# 220VAC_to_48V.net
KiCad netlist of a schematic drawn in Altium Designer
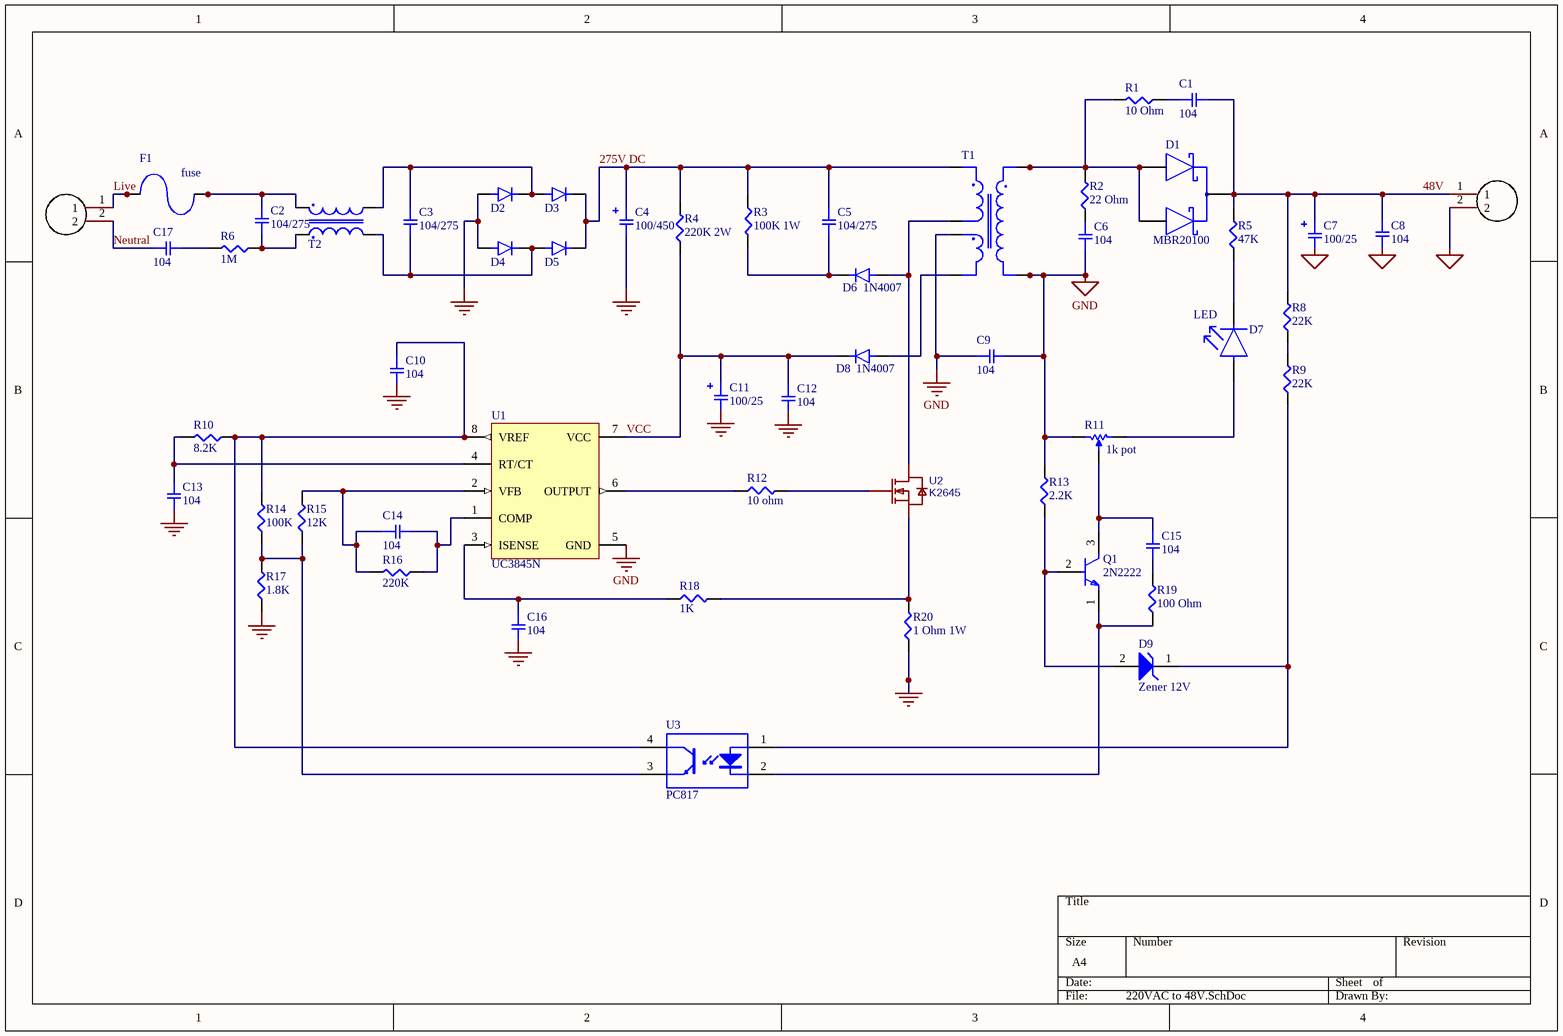
[diagram p0: 220VAC to 48V.SchDoc]

(export (version "E")
  (design (tool "Eeschema 10.0.6"))
  (components
    (comp (ref "C1") (value "104") (footprint "C-1") (libsource (lib "AC220_to_48V") (part "CAPACITOR 104")))
    (comp (ref "C2")
      (value "104/275")
      (footprint "C-15")
      (libsource (lib "AC220_to_48V") (part "CAPACITOR 104/275"))
    )
    (comp (ref "C3")
      (value "104/275")
      (footprint "C-15")
      (libsource (lib "AC220_to_48V") (part "CAPACITOR 104/275"))
    )
    (comp (ref "C4")
      (value "100/450")
      (footprint "C5B2.5")
      (libsource (lib "AC220_to_48V") (part "CAPACITOR 100/450"))
    )
    (comp (ref "C5")
      (value "104/275")
      (footprint "C-15")
      (libsource (lib "AC220_to_48V") (part "CAPACITOR 104/275"))
    )
    (comp (ref "C6") (value "104") (footprint "C-1") (libsource (lib "AC220_to_48V") (part "CAPACITOR 104")))
    (comp (ref "C7")
      (value "100/25")
      (footprint "C2.5-2")
      (libsource (lib "AC220_to_48V") (part "CAPACITOR 100/25"))
    )
    (comp (ref "C8") (value "104") (footprint "C-1") (libsource (lib "AC220_to_48V") (part "CAPACITOR 104")))
    (comp (ref "C9") (value "104") (footprint "C-1") (libsource (lib "AC220_to_48V") (part "CAPACITOR 104")))
    (comp (ref "C10") (value "104") (footprint "C-1") (libsource (lib "AC220_to_48V") (part "CAPACITOR 104")))
    (comp (ref "C11")
      (value "100/25")
      (footprint "C2.5-2")
      (libsource (lib "AC220_to_48V") (part "CAPACITOR 100/25"))
    )
    (comp (ref "C12") (value "104") (footprint "C-1") (libsource (lib "AC220_to_48V") (part "CAPACITOR 104")))
    (comp (ref "C13") (value "104") (footprint "C-1") (libsource (lib "AC220_to_48V") (part "CAPACITOR 104")))
    (comp (ref "C14") (value "104") (footprint "C-1") (libsource (lib "AC220_to_48V") (part "CAPACITOR 104")))
    (comp (ref "C15") (value "104") (footprint "C-1") (libsource (lib "AC220_to_48V") (part "CAPACITOR 104")))
    (comp (ref "C16") (value "104") (footprint "C-1") (libsource (lib "AC220_to_48V") (part "CAPACITOR 104")))
    (comp (ref "C17") (value "104") (footprint "C-1") (libsource (lib "AC220_to_48V") (part "CAPACITOR 104")))
    (comp (ref "CN1")
      (value "WJ2EDGRC-5.08-2P")
      (footprint "Terminal Block P5.08-2P")
      (fields (field (name "MANUFACTURER") "KANGNEX(康奈克斯电气)"))
      (libsource (lib "Terminal Block P5.08-2P") (part "WJ2EDGRC-5.08-2P"))
    )
    (comp (ref "CN2")
      (value "WJ2EDGRC-5.08-2P")
      (footprint "Terminal Block P5.08-2P")
      (fields (field (name "MANUFACTURER") "KANGNEX(康奈克斯电气)"))
      (libsource (lib "Terminal Block P5.08-2P") (part "WJ2EDGRC-5.08-2P"))
    )
    (comp (ref "D1")
      (value "MBR20100")
      (footprint "FP-MBR20100CT-E3-4W-MFG")
      (libsource (lib "MBR20100 schottky diode TH") (part "CMP-00030-42878425-1"))
    )
    (comp (ref "D2")
      (value "1N4007")
      (footprint "FP-1N4007-MFG")
      (description "DIODE GEN PURP 1KV 1A DO204AL")
      (fields
        (field (name "OCTOPART") "https://octopart.com/1n4007-e3%2F54-vishay-39548207")
        (field (name "MANUFACTURER") "Vishay")
      )
      (libsource (lib "1N4007") (part "CMP-02540-000046-1"))
    )
    (comp (ref "D3")
      (value "1N4007")
      (footprint "FP-1N4007-MFG")
      (description "DIODE GEN PURP 1KV 1A DO204AL")
      (fields
        (field (name "OCTOPART") "https://octopart.com/1n4007-e3%2F54-vishay-39548207")
        (field (name "MANUFACTURER") "Vishay")
      )
      (libsource (lib "1N4007") (part "CMP-02540-000046-1"))
    )
    (comp (ref "D4")
      (value "1N4007")
      (footprint "FP-1N4007-MFG")
      (description "DIODE GEN PURP 1KV 1A DO204AL")
      (fields
        (field (name "OCTOPART") "https://octopart.com/1n4007-e3%2F54-vishay-39548207")
        (field (name "MANUFACTURER") "Vishay")
      )
      (libsource (lib "1N4007") (part "CMP-02540-000046-1"))
    )
    (comp (ref "D5")
      (value "1N4007")
      (footprint "FP-1N4007-MFG")
      (description "DIODE GEN PURP 1KV 1A DO204AL")
      (fields
        (field (name "OCTOPART") "https://octopart.com/1n4007-e3%2F54-vishay-39548207")
        (field (name "MANUFACTURER") "Vishay")
      )
      (libsource (lib "1N4007") (part "CMP-02540-000046-1"))
    )
    (comp (ref "D6")
      (value "1N4007")
      (footprint "FP-1N4007-MFG")
      (description "DIODE GEN PURP 1KV 1A DO204AL")
      (fields
        (field (name "OCTOPART") "https://octopart.com/1n4007-e3%2F54-vishay-39548207")
        (field (name "MANUFACTURER") "Vishay")
      )
      (libsource (lib "1N4007") (part "CMP-02540-000046-1"))
    )
    (comp (ref "D7")
      (value "LED")
      (footprint "FP-HLMP-1719-MFG")
      (description "IR LED SFH480")
      (fields
        (field (name "MANUFACTURER") "Broadcom")
        (field (name "OCTOPART") "https://octopart.com/hlmp-1719-broadcom-71130405")
      )
      (libsource (lib "IR LED SFH480") (part "CMP-2000-06410-2"))
    )
    (comp (ref "D8")
      (value "1N4007")
      (footprint "FP-1N4007-MFG")
      (description "DIODE GEN PURP 1KV 1A DO204AL")
      (fields
        (field (name "OCTOPART") "https://octopart.com/1n4007-e3%2F54-vishay-39548207")
        (field (name "MANUFACTURER") "Vishay")
      )
      (libsource (lib "1N4007") (part "CMP-02540-000046-1"))
    )
    (comp (ref "D9")
      (value "Zener 12V")
      (footprint "ONSC-SURMETIC40-2-017AA-01")
      (description "Diode, Zener, Vr 12V, If 200mA, Pkg DO-41, Vf 1.2V, Tj +175C, Cs 380mA, Pd 1.3W, Ir 21mA")
      (fields (field (name "MANUFACTURER") "Vishay") (field (name "MANUFACTURER PART NUMBER") "1N4742A-TR"))
      (libsource (lib "1N4742 Zener 12V TH") (part "1N4742A-TR"))
    )
    (comp (ref "F1") (value "fuse") (footprint "SHK20L") (libsource (lib "AC220_to_48V") (part "fuse")))
    (comp (ref "Q1")
      (value "2N2222")
      (footprint "FP-JAN2N2222A-MFG")
      (description "TRANS NPN 50V 0.8A TO218")
      (libsource (lib "2N2222") (part "CMP-06366-000013-1"))
    )
    (comp (ref "R1")
      (value "10 Ohm")
      (footprint "R7-5")
      (libsource (lib "AC220_to_48V") (part "RESISTOR 1/4W"))
    )
    (comp (ref "R2")
      (value "22 Ohm")
      (footprint "R7-5")
      (libsource (lib "AC220_to_48V") (part "RESISTOR 1/4W"))
    )
    (comp (ref "R3")
      (value "100K 1W")
      (footprint "R-12,5")
      (libsource (lib "AC220_to_48V") (part "RESISTOR 2W"))
    )
    (comp (ref "R4")
      (value "220K 2W")
      (footprint "R-12,5")
      (libsource (lib "AC220_to_48V") (part "RESISTOR 2W"))
    )
    (comp (ref "R5") (value "47K") (footprint "R7-5") (libsource (lib "AC220_to_48V") (part "RESISTOR 1/4W")))
    (comp (ref "R6") (value "1M") (footprint "R7-5") (libsource (lib "AC220_to_48V") (part "RESISTOR 1/4W")))
    (comp (ref "R8") (value "22K") (footprint "R7-5") (libsource (lib "AC220_to_48V") (part "RESISTOR 1/4W")))
    (comp (ref "R9") (value "22K") (footprint "R7-5") (libsource (lib "AC220_to_48V") (part "RESISTOR 1/4W")))
    (comp (ref "R10")
      (value "8.2K")
      (footprint "R7-5")
      (libsource (lib "AC220_to_48V") (part "RESISTOR 1/4W"))
    )
    (comp (ref "R11")
      (value "1k pot")
      (footprint "BOUR-3296W-1-3")
      (description "Square Trimpot(R) Trimming Potentiometer, 1000 Ohm, -55 to 125 degC, 3-Pin THD, RoHS, Tube")
      (fields (field (name "TOLERANCE") "1%"))
      (libsource (lib "1k pot TH") (part "CMP-1747-00002-1"))
    )
    (comp (ref "R12")
      (value "10 ohm")
      (footprint "R7-5")
      (libsource (lib "AC220_to_48V") (part "RESISTOR 1/4W"))
    )
    (comp (ref "R13")
      (value "2.2K")
      (footprint "R7-5")
      (libsource (lib "AC220_to_48V") (part "RESISTOR 1/4W"))
    )
    (comp (ref "R14")
      (value "100K")
      (footprint "R7-5")
      (libsource (lib "AC220_to_48V") (part "RESISTOR 1/4W"))
    )
    (comp (ref "R15")
      (value "12K")
      (footprint "R7-5")
      (libsource (lib "AC220_to_48V") (part "RESISTOR 1/4W"))
    )
    (comp (ref "R16")
      (value "220K")
      (footprint "R7-5")
      (libsource (lib "AC220_to_48V") (part "RESISTOR 1/4W"))
    )
    (comp (ref "R17")
      (value "1.8K")
      (footprint "R7-5")
      (libsource (lib "AC220_to_48V") (part "RESISTOR 1/4W"))
    )
    (comp (ref "R18") (value "1K") (footprint "R7-5") (libsource (lib "AC220_to_48V") (part "RESISTOR 1/4W")))
    (comp (ref "R19")
      (value "100 Ohm")
      (footprint "R7-5")
      (libsource (lib "AC220_to_48V") (part "RESISTOR 1/4W"))
    )
    (comp (ref "R20")
      (value "1 Ohm 1W")
      (footprint "R-12,5")
      (libsource (lib "AC220_to_48V") (part "RESISTOR 2W"))
    )
    (comp (ref "T1")
      (value "Ideal Transformer With Central Tap")
      (footprint "ST-D1")
      (libsource (lib "AC220_to_48V") (part "Transformer With Central Tap Ideal_1"))
    )
    (comp (ref "T2")
      (value "common mode choke")
      (footprint "DFKH14")
      (libsource (lib "AC220_to_48V") (part "Transformer With Central Tap Ideal"))
    )
    (comp (ref "U1")
      (value "UC3845N")
      (footprint "P0008A")
      (fields (field (name "MANUFACTURER") "Texas Instruments"))
      (libsource (lib "UC3845AN") (part "CMP-0319-00305-2"))
    )
    (comp (ref "U2")
      (value "K2645")
      (footprint "TO-220-3_L10.5-W4.8-P2.54-L")
      (fields
        (field (name "MANUFACTURER") "VBsemi(微碧半导体)")
        (field (name "MANUFACTURER PART") "2SK2645-01MR-VB")
        (field (name "CONTRIBUTOR") "lcsc")
      )
      (libsource (lib "2SK2645") (part "2SK2645-01MR-VB"))
    )
    (comp (ref "U3")
      (value "PC817")
      (footprint "LTST-LTV-817-4")
      (fields (field (name "MANUFACTURER") "Lite-On"))
      (libsource (lib "PC817") (part "CMP-2000-06632-1"))
    )
  )
  (nets
    (net (code "1") (name "/48V") (class "Default")
      (node (ref "C1") (pin "2") (pinfunction "2_2") (pintype "passive"))
      (node (ref "C7") (pin "1") (pinfunction "1_1") (pintype "passive"))
      (node (ref "C8") (pin "2") (pinfunction "2_2") (pintype "passive"))
      (node (ref "CN1") (pin "1") (pinfunction "1_1") (pintype "passive"))
      (node (ref "D1") (pin "2") (pinfunction "COMMON_CATHODE_2") (pintype "passive"))
      (node (ref "R5") (pin "2") (pinfunction "2_2") (pintype "passive"))
      (node (ref "R8") (pin "2") (pinfunction "2_2") (pintype "passive"))
    )
    (net (code "2") (name "/275V DC") (class "Default")
      (node (ref "C4") (pin "1") (pinfunction "1_1") (pintype "passive"))
      (node (ref "C5") (pin "1") (pinfunction "1_1") (pintype "passive"))
      (node (ref "D3") (pin "1") (pinfunction "C_1") (pintype "passive"))
      (node (ref "D5") (pin "1") (pinfunction "C_1") (pintype "passive"))
      (node (ref "R3") (pin "1") (pinfunction "1_1") (pintype "passive"))
      (node (ref "R4") (pin "2") (pinfunction "2_2") (pintype "passive"))
      (node (ref "T1") (pin "7") (pinfunction "7_7") (pintype "passive"))
    )
    (net (code "3") (name "/Live") (class "Default")
      (node (ref "CN2") (pin "1") (pinfunction "1_1") (pintype "passive"))
      (node (ref "F1") (pin "1A") (pinfunction "1A_1A") (pintype "passive"))
      (node (ref "F1") (pin "1B") (pinfunction "1B_1B") (pintype "passive"))
    )
    (net (code "4") (name "/Neutral") (class "Default")
      (node (ref "C17") (pin "1") (pinfunction "1_1") (pintype "passive"))
      (node (ref "CN2") (pin "2") (pinfunction "2_2") (pintype "passive"))
    )
    (net (code "5") (name "/VCC") (class "Default")
      (node (ref "C11") (pin "1") (pinfunction "1_1") (pintype "passive"))
      (node (ref "C12") (pin "1") (pinfunction "1_1") (pintype "passive"))
      (node (ref "D8") (pin "1") (pinfunction "C_1") (pintype "passive"))
      (node (ref "R4") (pin "1") (pinfunction "1_1") (pintype "passive"))
      (node (ref "U1") (pin "7") (pinfunction "VCC_7") (pintype "power_in"))
    )
    (net (code "6") (name "GND") (class "Default")
      (node (ref "C10") (pin "2") (pinfunction "2_2") (pintype "passive"))
      (node (ref "C11") (pin "2") (pinfunction "2_2") (pintype "passive"))
      (node (ref "C12") (pin "2") (pinfunction "2_2") (pintype "passive"))
      (node (ref "C13") (pin "1") (pinfunction "1_1") (pintype "passive"))
      (node (ref "C16") (pin "2") (pinfunction "2_2") (pintype "passive"))
      (node (ref "C4") (pin "2") (pinfunction "2_2") (pintype "passive"))
      (node (ref "C6") (pin "2") (pinfunction "2_2") (pintype "passive"))
      (node (ref "C7") (pin "2") (pinfunction "2_2") (pintype "passive"))
      (node (ref "C8") (pin "1") (pinfunction "1_1") (pintype "passive"))
      (node (ref "C9") (pin "1") (pinfunction "1_1") (pintype "passive"))
      (node (ref "C9") (pin "2") (pinfunction "2_2") (pintype "passive"))
      (node (ref "CN1") (pin "2") (pinfunction "2_2") (pintype "passive"))
      (node (ref "D2") (pin "2") (pinfunction "A_2") (pintype "passive"))
      (node (ref "D4") (pin "2") (pinfunction "A_2") (pintype "passive"))
      (node (ref "R11") (pin "3") (pinfunction "B_3") (pintype "passive"))
      (node (ref "R13") (pin "2") (pinfunction "2_2") (pintype "passive"))
      (node (ref "R17") (pin "1") (pinfunction "1_1") (pintype "passive"))
      (node (ref "R20") (pin "1") (pinfunction "1_1") (pintype "passive"))
      (node (ref "T1") (pin "1") (pinfunction "1_1") (pintype "passive"))
      (node (ref "T1") (pin "2") (pinfunction "2_2") (pintype "passive"))
      (node (ref "T1") (pin "8") (pinfunction "8_8") (pintype "passive"))
      (node (ref "U1") (pin "5") (pinfunction "GND_5") (pintype "power_in"))
    )
    (net (code "7") (name "Net-(C1-Pad1)") (class "Default")
      (node (ref "C1") (pin "1") (pinfunction "1_1") (pintype "passive"))
      (node (ref "R1") (pin "1") (pinfunction "1_1") (pintype "passive"))
    )
    (net (code "8") (name "Net-(C2-Pad1)") (class "Default")
      (node (ref "C2") (pin "1") (pinfunction "1_1") (pintype "passive"))
      (node (ref "F1") (pin "2A") (pinfunction "2A_2A") (pintype "passive"))
      (node (ref "F1") (pin "2B") (pinfunction "2B_2B") (pintype "passive"))
      (node (ref "T2") (pin "4") (pinfunction "4_4") (pintype "passive"))
    )
    (net (code "9") (name "Net-(C2-Pad2)") (class "Default")
      (node (ref "C2") (pin "2") (pinfunction "2_2") (pintype "passive"))
      (node (ref "R6") (pin "1") (pinfunction "1_1") (pintype "passive"))
      (node (ref "T2") (pin "1") (pinfunction "1_1") (pintype "passive"))
    )
    (net (code "10") (name "Net-(C6-Pad1)") (class "Default")
      (node (ref "C6") (pin "1") (pinfunction "1_1") (pintype "passive"))
      (node (ref "R2") (pin "1") (pinfunction "1_1") (pintype "passive"))
    )
    (net (code "11") (name "Net-(C15-Pad2)") (class "Default")
      (node (ref "C15") (pin "2") (pinfunction "2_2") (pintype "passive"))
      (node (ref "R19") (pin "2") (pinfunction "2_2") (pintype "passive"))
    )
    (net (code "12") (name "Net-(C17-Pad2)") (class "Default")
      (node (ref "C17") (pin "2") (pinfunction "2_2") (pintype "passive"))
      (node (ref "R6") (pin "2") (pinfunction "2_2") (pintype "passive"))
    )
    (net (code "13") (name "Net-(D1-1_ANODE)") (class "Default")
      (node (ref "D1") (pin "1") (pinfunction "1_ANODE_1") (pintype "passive"))
      (node (ref "D1") (pin "3") (pinfunction "2_ANODE_3") (pintype "passive"))
      (node (ref "R1") (pin "2") (pinfunction "2_2") (pintype "passive"))
      (node (ref "T1") (pin "5") (pinfunction "5_5") (pintype "passive"))
      (node (ref "T1") (pin "6") (pinfunction "6_6") (pintype "passive"))
    )
    (net (code "14") (name "Net-(D2-C)") (class "Default")
      (node (ref "C3") (pin "1") (pinfunction "1_1") (pintype "passive"))
      (node (ref "D2") (pin "1") (pinfunction "C_1") (pintype "passive"))
      (node (ref "D3") (pin "2") (pinfunction "A_2") (pintype "passive"))
      (node (ref "T2") (pin "3") (pinfunction "3_3") (pintype "passive"))
    )
    (net (code "15") (name "Net-(D4-C)") (class "Default")
      (node (ref "C3") (pin "2") (pinfunction "2_2") (pintype "passive"))
      (node (ref "D4") (pin "1") (pinfunction "C_1") (pintype "passive"))
      (node (ref "D5") (pin "2") (pinfunction "A_2") (pintype "passive"))
      (node (ref "T2") (pin "2") (pinfunction "2_2") (pintype "passive"))
    )
    (net (code "16") (name "Net-(D6-A)") (class "Default")
      (node (ref "D6") (pin "2") (pinfunction "A_2") (pintype "passive"))
      (node (ref "T1") (pin "9") (pinfunction "9_9") (pintype "passive"))
      (node (ref "U2") (pin "2") (pinfunction "D_2") (pintype "passive"))
    )
    (net (code "17") (name "Net-(D6-C)") (class "Default")
      (node (ref "C5") (pin "2") (pinfunction "2_2") (pintype "passive"))
      (node (ref "D6") (pin "1") (pinfunction "C_1") (pintype "passive"))
      (node (ref "R3") (pin "2") (pinfunction "2_2") (pintype "passive"))
    )
    (net (code "18") (name "Net-(D7-A)") (class "Default")
      (node (ref "D7") (pin "2") (pinfunction "A_2") (pintype "passive"))
      (node (ref "R11") (pin "1") (pinfunction "A_1") (pintype "passive"))
    )
    (net (code "19") (name "Net-(D7-C)") (class "Default")
      (node (ref "D7") (pin "1") (pinfunction "C_1") (pintype "passive"))
      (node (ref "R5") (pin "1") (pinfunction "1_1") (pintype "passive"))
    )
    (net (code "20") (name "Net-(D8-A)") (class "Default")
      (node (ref "D8") (pin "2") (pinfunction "A_2") (pintype "passive"))
      (node (ref "T1") (pin "12") (pinfunction "12_12") (pintype "passive"))
    )
    (net (code "21") (name "Net-(D9-A)") (class "Default")
      (node (ref "D9") (pin "2") (pinfunction "A_2") (pintype "passive"))
      (node (ref "Q1") (pin "2") (pinfunction "B_2") (pintype "passive"))
      (node (ref "R13") (pin "1") (pinfunction "1_1") (pintype "passive"))
    )
    (net (code "22") (name "Net-(D9-K)") (class "Default")
      (node (ref "D9") (pin "1") (pinfunction "K_1") (pintype "passive"))
      (node (ref "R9") (pin "1") (pinfunction "1_1") (pintype "passive"))
      (node (ref "U3") (pin "1") (pinfunction "ANODE_1") (pintype "passive"))
    )
    (net (code "23") (name "Net-(Q1-C)") (class "Default")
      (node (ref "C15") (pin "1") (pinfunction "1_1") (pintype "passive"))
      (node (ref "Q1") (pin "3") (pinfunction "C_3") (pintype "passive"))
      (node (ref "R11") (pin "2") (pinfunction "TAP_2") (pintype "passive"))
    )
    (net (code "24") (name "Net-(Q1-E)") (class "Default")
      (node (ref "Q1") (pin "1") (pinfunction "E_1") (pintype "passive"))
      (node (ref "R19") (pin "1") (pinfunction "1_1") (pintype "passive"))
      (node (ref "U3") (pin "2") (pinfunction "CATHODE_2") (pintype "passive"))
    )
    (net (code "25") (name "Net-(R8-Pad1)") (class "Default")
      (node (ref "R8") (pin "1") (pinfunction "1_1") (pintype "passive"))
      (node (ref "R9") (pin "2") (pinfunction "2_2") (pintype "passive"))
    )
    (net (code "26") (name "Net-(U1-COMP)") (class "Default")
      (node (ref "C14") (pin "2") (pinfunction "2_2") (pintype "passive"))
      (node (ref "R16") (pin "1") (pinfunction "1_1") (pintype "passive"))
      (node (ref "U1") (pin "1") (pinfunction "COMP_1") (pintype "passive"))
    )
    (net (code "27") (name "Net-(U1-ISENSE)") (class "Default")
      (node (ref "C16") (pin "1") (pinfunction "1_1") (pintype "passive"))
      (node (ref "R18") (pin "1") (pinfunction "1_1") (pintype "passive"))
      (node (ref "U1") (pin "3") (pinfunction "ISENSE_3") (pintype "input"))
    )
    (net (code "28") (name "Net-(U1-OUTPUT)") (class "Default")
      (node (ref "R12") (pin "1") (pinfunction "1_1") (pintype "passive"))
      (node (ref "U1") (pin "6") (pinfunction "OUTPUT_6") (pintype "output"))
    )
    (net (code "29") (name "Net-(U1-RT{slash}CT)") (class "Default")
      (node (ref "C13") (pin "2") (pinfunction "2_2") (pintype "passive"))
      (node (ref "R10") (pin "2") (pinfunction "2_2") (pintype "passive"))
      (node (ref "U1") (pin "4") (pinfunction "RT/CT_4") (pintype "passive"))
    )
    (net (code "30") (name "Net-(U1-VFB)") (class "Default")
      (node (ref "C14") (pin "1") (pinfunction "1_1") (pintype "passive"))
      (node (ref "R15") (pin "2") (pinfunction "2_2") (pintype "passive"))
      (node (ref "R16") (pin "2") (pinfunction "2_2") (pintype "passive"))
      (node (ref "U1") (pin "2") (pinfunction "VFB_2") (pintype "input"))
    )
    (net (code "31") (name "Net-(U1-VREF)") (class "Default")
      (node (ref "C10") (pin "1") (pinfunction "1_1") (pintype "passive"))
      (node (ref "R10") (pin "1") (pinfunction "1_1") (pintype "passive"))
      (node (ref "R14") (pin "2") (pinfunction "2_2") (pintype "passive"))
      (node (ref "U1") (pin "8") (pinfunction "VREF_8") (pintype "output"))
      (node (ref "U3") (pin "4") (pinfunction "COLLECTOR_4") (pintype "passive"))
    )
    (net (code "32") (name "Net-(U2-G)") (class "Default")
      (node (ref "R12") (pin "2") (pinfunction "2_2") (pintype "passive"))
      (node (ref "U2") (pin "1") (pinfunction "G_1") (pintype "passive"))
    )
    (net (code "33") (name "Net-(U2-S)") (class "Default")
      (node (ref "R18") (pin "2") (pinfunction "2_2") (pintype "passive"))
      (node (ref "R20") (pin "2") (pinfunction "2_2") (pintype "passive"))
      (node (ref "U2") (pin "3") (pinfunction "S_3") (pintype "passive"))
    )
    (net (code "34") (name "Net-(U3-EMITTER)") (class "Default")
      (node (ref "R14") (pin "1") (pinfunction "1_1") (pintype "passive"))
      (node (ref "R15") (pin "1") (pinfunction "1_1") (pintype "passive"))
      (node (ref "R17") (pin "2") (pinfunction "2_2") (pintype "passive"))
      (node (ref "U3") (pin "3") (pinfunction "EMITTER_3") (pintype "passive"))
    )
    (net (code "35") (name "unconnected-(R2-Pad2)") (class "Default")
      (node (ref "R2") (pin "2") (pinfunction "2_2") (pintype "passive"))
    )
  )
)
